# Buzzer_LED.net
KiCad netlist of a schematic drawn in Altium Designer
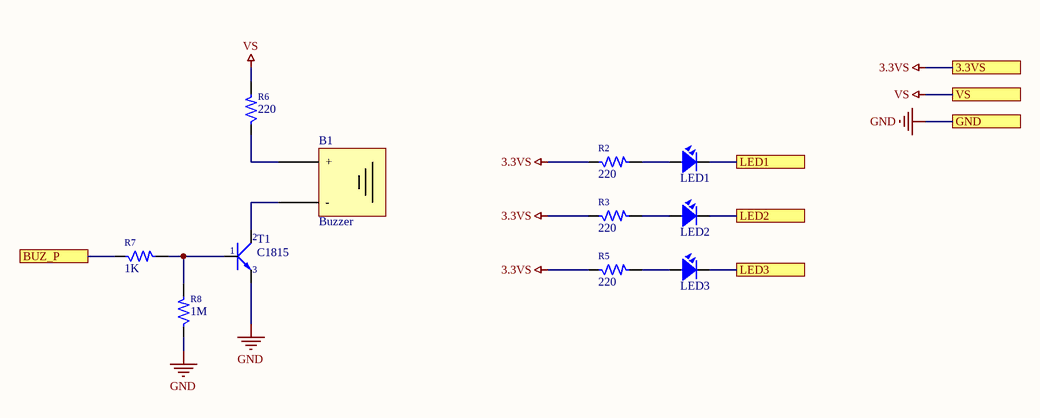
[diagram p0: Buzzer_LED.SchDoc]

(export (version "E")
  (design (tool "Eeschema 10.0.6"))
  (components
    (comp (ref "B1")
      (value "Buzzer")
      (footprint "Buzzer")
      (description "12xx")
      (libsource (lib "MicroMouse") (part "Buzzer"))
    )
    (comp (ref "LED1")
      (value "LED SMD")
      (footprint "SM-LED-0805-Blue")
      (libsource (lib "MicroMouse") (part "LED-SMD-0805"))
    )
    (comp (ref "LED2")
      (value "LED SMD")
      (footprint "SM-LED-0805-Blue")
      (libsource (lib "MicroMouse") (part "LED-SMD-0805"))
    )
    (comp (ref "LED3")
      (value "LED SMD")
      (footprint "SM-LED-0805-Blue")
      (libsource (lib "MicroMouse") (part "LED-SMD-0805"))
    )
    (comp (ref "R2")
      (value "220")
      (footprint "RESC2012X70N")
      (description "Res 0805")
      (libsource (lib "MicroMouse") (part "Res SMD"))
    )
    (comp (ref "R3")
      (value "220")
      (footprint "RESC2012X70N")
      (description "Res 0805")
      (libsource (lib "MicroMouse") (part "Res SMD"))
    )
    (comp (ref "R5")
      (value "220")
      (footprint "RESC2012X70N")
      (description "Res 0805")
      (libsource (lib "MicroMouse") (part "Res SMD"))
    )
    (comp (ref "R6")
      (value "220")
      (footprint "RESC2012X70N")
      (description "Res 0805")
      (libsource (lib "MicroMouse") (part "Res SMD"))
    )
    (comp (ref "R7")
      (value "1K")
      (footprint "RESC2012X70N")
      (description "Res 0805")
      (libsource (lib "MicroMouse") (part "Res SMD"))
    )
    (comp (ref "R8")
      (value "1M")
      (footprint "RESC2012X70N")
      (description "Res 0805")
      (libsource (lib "MicroMouse") (part "Res SMD"))
    )
    (comp (ref "T1") (value "C1815") (footprint "SOT23-3") (libsource (lib "TVTinh_Library") (part "NPN SM")))
  )
  (nets
    (net (code "1") (name "/BUZ_P") (class "Default")
      (node (ref "R7") (pin "1") (pinfunction "1_1") (pintype "passive"))
    )
    (net (code "2") (name "/LED1") (class "Default")
      (node (ref "LED1") (pin "2") (pinfunction "2_2") (pintype "passive"))
    )
    (net (code "3") (name "/LED2") (class "Default")
      (node (ref "LED2") (pin "2") (pinfunction "2_2") (pintype "passive"))
    )
    (net (code "4") (name "/LED3") (class "Default")
      (node (ref "LED3") (pin "2") (pinfunction "2_2") (pintype "passive"))
    )
    (net (code "5") (name "3.3VS") (class "Default")
      (node (ref "R2") (pin "1") (pinfunction "1_1") (pintype "passive"))
      (node (ref "R3") (pin "1") (pinfunction "1_1") (pintype "passive"))
      (node (ref "R5") (pin "1") (pinfunction "1_1") (pintype "passive"))
    )
    (net (code "6") (name "GND") (class "Default")
      (node (ref "R8") (pin "1") (pinfunction "1_1") (pintype "passive"))
      (node (ref "T1") (pin "2") (pinfunction "E_2") (pintype "passive"))
    )
    (net (code "7") (name "Net-(B1-Pad+)") (class "Default")
      (node (ref "B1") (pin "+") (pinfunction "+_+") (pintype "passive"))
      (node (ref "R6") (pin "1") (pinfunction "1_1") (pintype "passive"))
    )
    (net (code "8") (name "Net-(LED1-Pad1)") (class "Default")
      (node (ref "LED1") (pin "1") (pinfunction "1_1") (pintype "passive"))
      (node (ref "R2") (pin "2") (pinfunction "2_2") (pintype "passive"))
    )
    (net (code "9") (name "Net-(LED2-Pad1)") (class "Default")
      (node (ref "LED2") (pin "1") (pinfunction "1_1") (pintype "passive"))
      (node (ref "R3") (pin "2") (pinfunction "2_2") (pintype "passive"))
    )
    (net (code "10") (name "Net-(LED3-Pad1)") (class "Default")
      (node (ref "LED3") (pin "1") (pinfunction "1_1") (pintype "passive"))
      (node (ref "R5") (pin "2") (pinfunction "2_2") (pintype "passive"))
    )
    (net (code "11") (name "Net-(T1-B)") (class "Default")
      (node (ref "R7") (pin "2") (pinfunction "2_2") (pintype "passive"))
      (node (ref "R8") (pin "2") (pinfunction "2_2") (pintype "passive"))
      (node (ref "T1") (pin "1") (pinfunction "B_1") (pintype "passive"))
    )
    (net (code "12") (name "Net-(T1-C)") (class "Default")
      (node (ref "B1") (pin "-") (pinfunction "-_-") (pintype "passive"))
      (node (ref "T1") (pin "3") (pinfunction "C_3") (pintype "passive"))
    )
    (net (code "13") (name "VS") (class "Default")
      (node (ref "R6") (pin "2") (pinfunction "2_2") (pintype "passive"))
    )
  )
)
